# Communication.net
KiCad netlist of a schematic drawn in Altium Designer
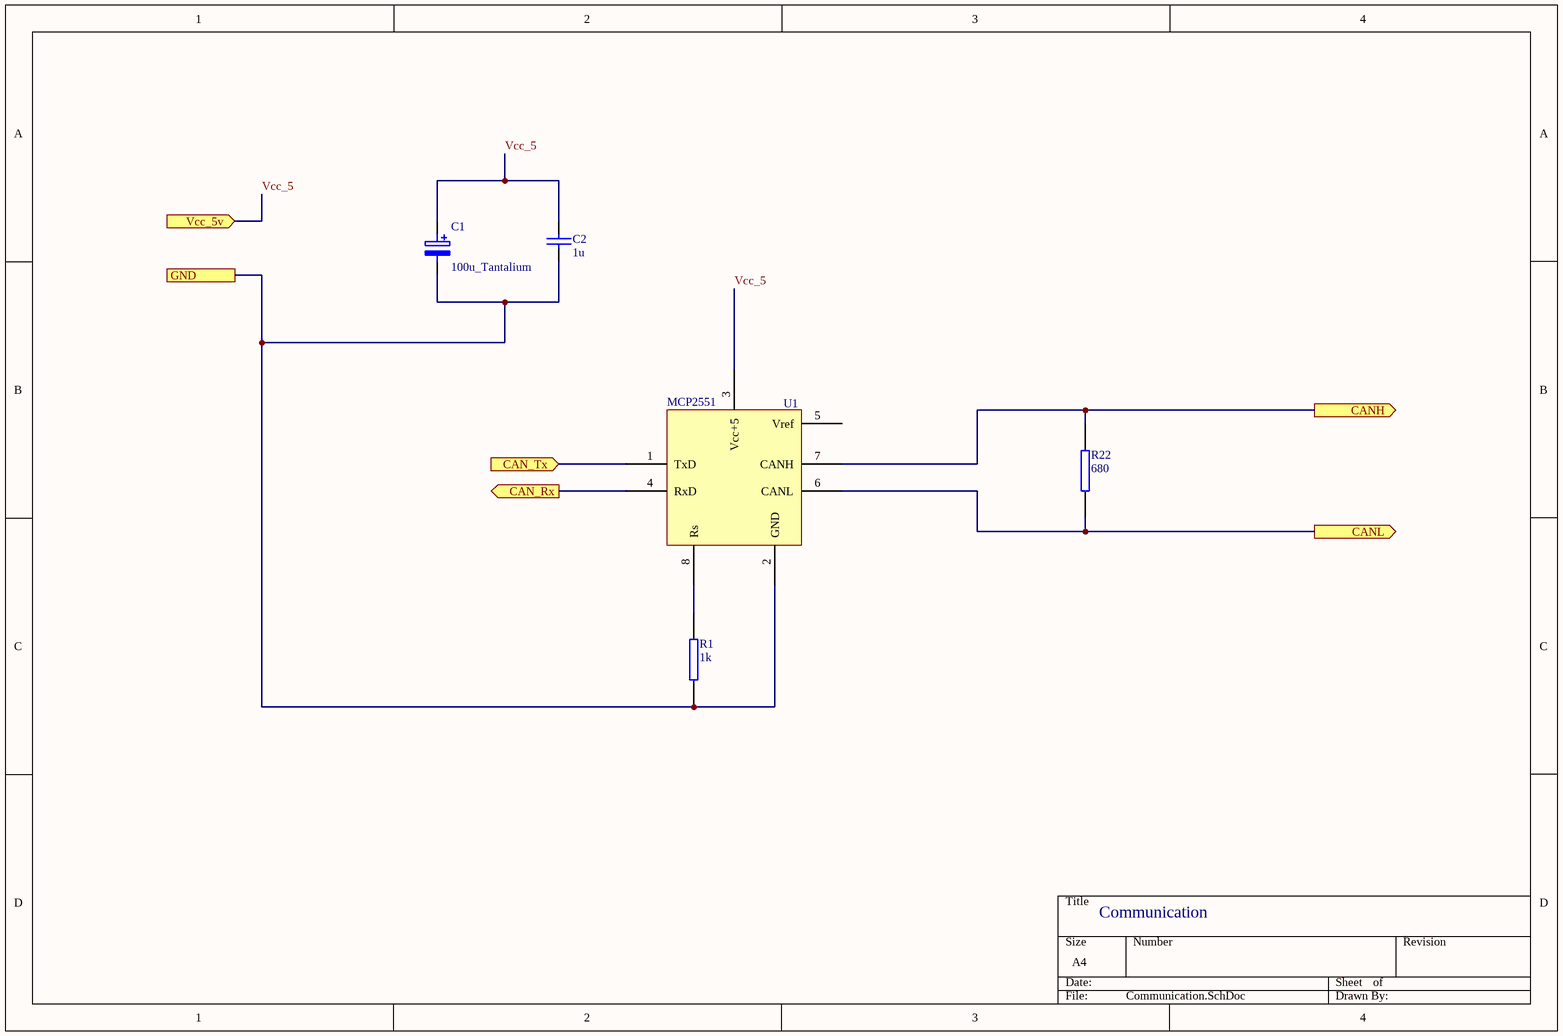
[diagram p0: Communication.SchDoc]

(export (version "E")
  (design (tool "Eeschema 10.0.6"))
  (components
    (comp (ref "C1")
      (value "100u_Tantalium")
      (footprint "Tantalum_9545")
      (libsource (lib "Sch_Lib_24") (part "CAP_ELECTRO"))
    )
    (comp (ref "C2")
      (value "1u")
      (footprint "1206_SMD")
      (description "Capacitor")
      (libsource (lib "Sch_Lib_24") (part "CAP"))
    )
    (comp (ref "R1") (value "1k") (footprint "1206_SMD") (libsource (lib "Sch_Lib_24") (part "RES2")))
    (comp (ref "R22") (value "680") (footprint "1206_SMD") (libsource (lib "Sch_Lib_24") (part "RES2")))
    (comp (ref "U1")
      (value "MCP2551")
      (footprint "SOIC8")
      (libsource (lib "Sch_Lib_24") (part "CAN_Interface"))
    )
  )
  (nets
    (net (code "1") (name "/CANH") (class "Default")
      (node (ref "R22") (pin "2") (pinfunction "2_2") (pintype "passive"))
      (node (ref "U1") (pin "7") (pinfunction "CANH_7") (pintype "passive"))
    )
    (net (code "2") (name "/CANL") (class "Default")
      (node (ref "R22") (pin "1") (pinfunction "1_1") (pintype "passive"))
      (node (ref "U1") (pin "6") (pinfunction "CANL_6") (pintype "passive"))
    )
    (net (code "3") (name "/CAN_Rx") (class "Default")
      (node (ref "U1") (pin "4") (pinfunction "RxD_4") (pintype "passive"))
    )
    (net (code "4") (name "/CAN_Tx") (class "Default")
      (node (ref "U1") (pin "1") (pinfunction "TxD_1") (pintype "passive"))
    )
    (net (code "5") (name "/GND") (class "Default")
      (node (ref "C1") (pin "2") (pintype "passive"))
      (node (ref "C2") (pin "2") (pinfunction "2_2") (pintype "passive"))
      (node (ref "R1") (pin "1") (pinfunction "1_1") (pintype "passive"))
      (node (ref "U1") (pin "2") (pinfunction "GND_2") (pintype "passive"))
    )
    (net (code "6") (name "/Vcc_5") (class "Default")
      (node (ref "C1") (pin "1") (pintype "passive"))
      (node (ref "C2") (pin "1") (pinfunction "1_1") (pintype "passive"))
      (node (ref "U1") (pin "3") (pinfunction "Vcc+5_3") (pintype "passive"))
    )
    (net (code "7") (name "Net-(U1-Rs)") (class "Default")
      (node (ref "R1") (pin "2") (pinfunction "2_2") (pintype "passive"))
      (node (ref "U1") (pin "8") (pinfunction "Rs_8") (pintype "passive"))
    )
    (net (code "8") (name "unconnected-(U1-Vref-Pad5)") (class "Default")
      (node (ref "U1") (pin "5") (pinfunction "Vref_5") (pintype "passive"))
    )
  )
)
